# Card_Edge_Connector.net
KiCad netlist of a schematic drawn in Altium Designer
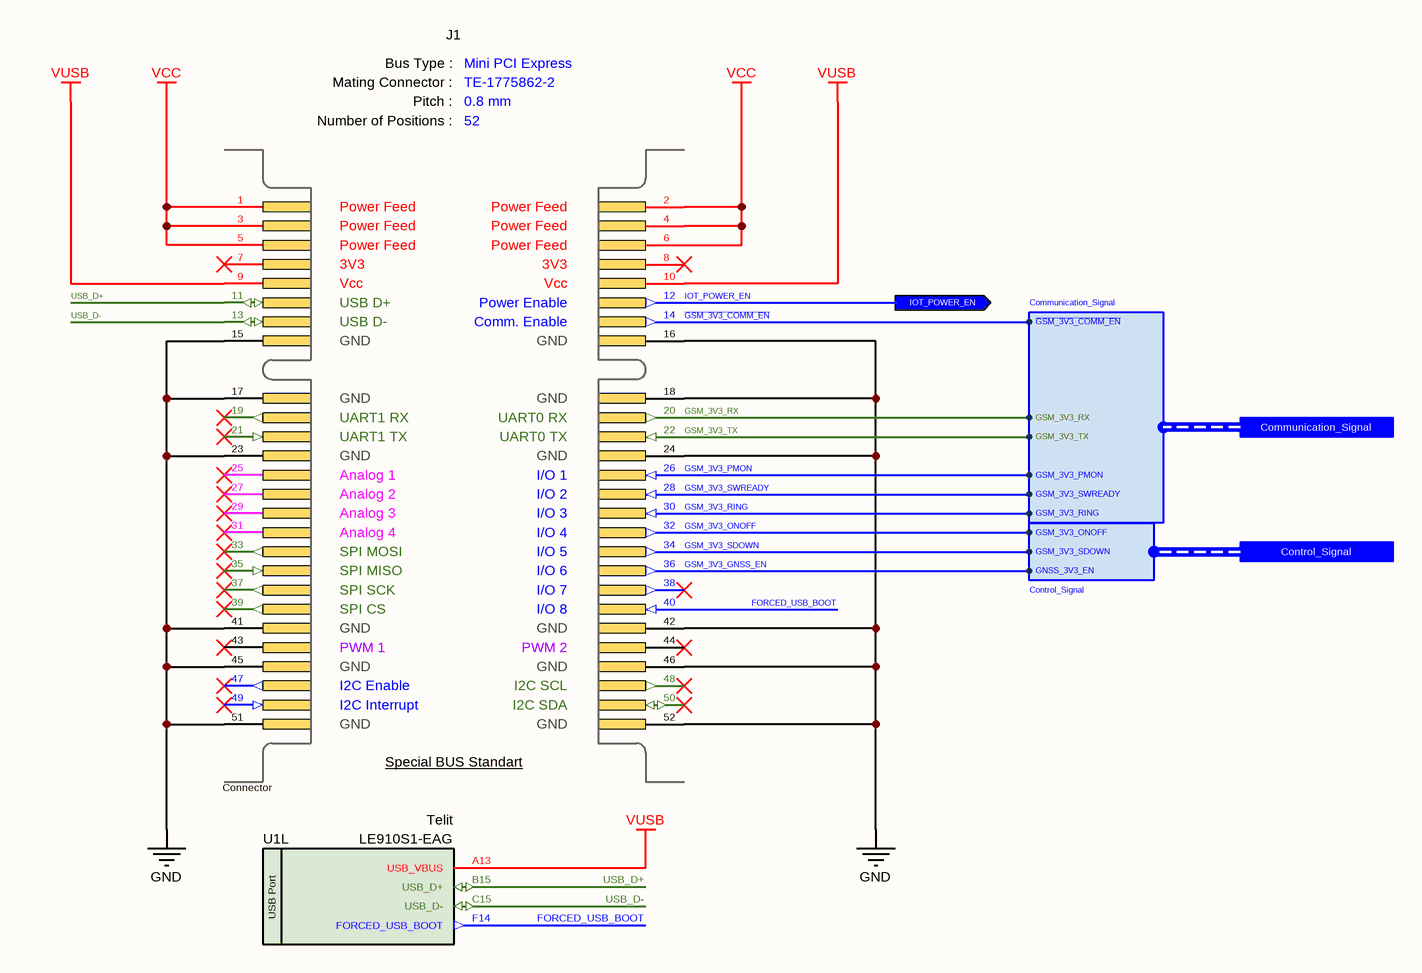
[diagram p0: Card Edge Connector.SchDoc]

(export (version "E")
  (design (tool "Eeschema 10.0.6"))
  (components
    (comp (ref "J1")
      (value "Connector - Mini PCI-E [Add-on]")
      (footprint "PCB - Mini PCI Express")
      (description "Mini PCI-Express gold finger connector.")
      (fields
        (field (name "BUS TYPE") "Mini PCI Express")
        (field (name "MATING CONNECTOR") "TE-1775862-2")
        (field (name "PITCH") "0.8 mm")
        (field (name "NUMBER OF POSITIONS") "52")
        (field (name "SYSTEM") "Connector")
      )
      (libsource (lib "P101DA_Library") (part "Connector - Mini PCI-E [Add-on]"))
    )
    (comp (ref "U1")
      (value "LE910S1-EAG LTE GSM Module")
      (footprint "LE910 GSM Modem")
      (description "Telit LE910S1-EAG GPRS/GNSS Module")
      (fields
        (field (name "MANUFACTURER PART NUMBER") "LE910S1-EAG")
        (field (name "MANUFACTURER NAME") "Telit")
      )
      (libsource (lib "P101DA_Library") (part "IC - LE910S1-EAG"))
    )
  )
  (nets
    (net (code "4") (name "/FORCED_USB_BOOT") (class "Default")
      (node (ref "J1") (pin "40") (pinfunction "Pin-40_40") (pintype "input"))
      (node (ref "U1") (pin "F14") (pinfunction "FORCED_USB_BOOT_F14") (pintype "output"))
    )
    (net (code "5") (name "/GSM_3V3_GNSS_EN") (class "Default")
      (node (ref "J1") (pin "36") (pinfunction "Pin-36_36") (pintype "output"))
    )
    (net (code "6") (name "/GSM_3V3_ONOFF") (class "Default")
      (node (ref "J1") (pin "32") (pinfunction "Pin-32_32") (pintype "output"))
    )
    (net (code "7") (name "/GSM_3V3_PMON") (class "Default")
      (node (ref "J1") (pin "26") (pinfunction "Pin-26_26") (pintype "input"))
    )
    (net (code "8") (name "/GSM_3V3_RING") (class "Default")
      (node (ref "J1") (pin "30") (pinfunction "Pin-30_30") (pintype "input"))
    )
    (net (code "9") (name "/GSM_3V3_RX") (class "Default")
      (node (ref "J1") (pin "20") (pinfunction "Pin-20_20") (pintype "output"))
    )
    (net (code "10") (name "/GSM_3V3_SDOWN") (class "Default")
      (node (ref "J1") (pin "34") (pinfunction "Pin-34_34") (pintype "output"))
    )
    (net (code "11") (name "/GSM_3V3_SWREADY") (class "Default")
      (node (ref "J1") (pin "28") (pinfunction "Pin-28_28") (pintype "input"))
    )
    (net (code "12") (name "/GSM_3V3_TX") (class "Default")
      (node (ref "J1") (pin "22") (pinfunction "Pin-22_22") (pintype "input"))
    )
    (net (code "13") (name "/IOT_POWER_EN") (class "Default")
      (node (ref "J1") (pin "12") (pinfunction "Pin-12_12") (pintype "output"))
    )
    (net (code "14") (name "/USB_D+") (class "Default")
      (node (ref "J1") (pin "11") (pinfunction "Pin-11_11") (pintype "bidirectional"))
      (node (ref "U1") (pin "B15") (pinfunction "USB_D+_B15") (pintype "bidirectional"))
    )
    (net (code "15") (name "/USB_D-") (class "Default")
      (node (ref "J1") (pin "13") (pinfunction "Pin-13_13") (pintype "bidirectional"))
      (node (ref "U1") (pin "C15") (pinfunction "USB_D-_C15") (pintype "bidirectional"))
    )
    (net (code "17") (name "/~{GSM_3V3_COMM_EN}") (class "Default")
      (node (ref "J1") (pin "14") (pinfunction "Pin-14_14") (pintype "output"))
    )
    (net (code "18") (name "GND") (class "Default")
      (node (ref "J1") (pin "15") (pinfunction "Pin-15_15") (pintype "power_in"))
      (node (ref "J1") (pin "16") (pinfunction "Pin-16_16") (pintype "power_in"))
      (node (ref "J1") (pin "17") (pinfunction "Pin-17_17") (pintype "power_in"))
      (node (ref "J1") (pin "18") (pinfunction "Pin-18_18") (pintype "power_in"))
      (node (ref "J1") (pin "23") (pinfunction "Pin-23_23") (pintype "power_in"))
      (node (ref "J1") (pin "24") (pinfunction "Pin-24_24") (pintype "power_in"))
      (node (ref "J1") (pin "41") (pinfunction "Pin-41_41") (pintype "power_in"))
      (node (ref "J1") (pin "42") (pinfunction "Pin-42_42") (pintype "power_in"))
      (node (ref "J1") (pin "45") (pinfunction "Pin-45_45") (pintype "power_in"))
      (node (ref "J1") (pin "46") (pinfunction "Pin-46_46") (pintype "power_in"))
      (node (ref "J1") (pin "51") (pinfunction "Pin-51_51") (pintype "power_in"))
      (node (ref "J1") (pin "52") (pinfunction "Pin-52_52") (pintype "power_in"))
    )
    (net (code "19") (name "VCC") (class "Default")
      (node (ref "J1") (pin "1") (pinfunction "Pin-1_1") (pintype "power_in"))
      (node (ref "J1") (pin "2") (pinfunction "Pin-2_2") (pintype "power_in"))
      (node (ref "J1") (pin "3") (pinfunction "Pin-3_3") (pintype "power_in"))
      (node (ref "J1") (pin "4") (pinfunction "Pin-4_4") (pintype "power_in"))
      (node (ref "J1") (pin "5") (pinfunction "Pin-5_5") (pintype "power_in"))
      (node (ref "J1") (pin "6") (pinfunction "Pin-6_6") (pintype "power_in"))
    )
    (net (code "20") (name "VUSB") (class "Default")
      (node (ref "J1") (pin "10") (pinfunction "Pin-10_10") (pintype "power_in"))
      (node (ref "J1") (pin "9") (pinfunction "Pin-9_9") (pintype "power_in"))
      (node (ref "U1") (pin "A13") (pinfunction "USB_VBUS_A13") (pintype "power_in"))
    )
    (net (code "21") (name "unconnected-(J1-Pin-7-Pad7)") (class "Default")
      (node (ref "J1") (pin "7") (pinfunction "Pin-7_7") (pintype "power_in+no_connect"))
    )
    (net (code "22") (name "unconnected-(J1-Pin-8-Pad8)") (class "Default")
      (node (ref "J1") (pin "8") (pinfunction "Pin-8_8") (pintype "power_in+no_connect"))
    )
    (net (code "23") (name "unconnected-(J1-Pin-19-Pad19)") (class "Default")
      (node (ref "J1") (pin "19") (pinfunction "Pin-19_19") (pintype "output+no_connect"))
    )
    (net (code "24") (name "unconnected-(J1-Pin-21-Pad21)") (class "Default")
      (node (ref "J1") (pin "21") (pinfunction "Pin-21_21") (pintype "input+no_connect"))
    )
    (net (code "25") (name "unconnected-(J1-Pin-25-Pad25)") (class "Default")
      (node (ref "J1") (pin "25") (pinfunction "Pin-25_25") (pintype "passive+no_connect"))
    )
    (net (code "26") (name "unconnected-(J1-Pin-27-Pad27)") (class "Default")
      (node (ref "J1") (pin "27") (pinfunction "Pin-27_27") (pintype "passive+no_connect"))
    )
    (net (code "27") (name "unconnected-(J1-Pin-29-Pad29)") (class "Default")
      (node (ref "J1") (pin "29") (pinfunction "Pin-29_29") (pintype "passive+no_connect"))
    )
    (net (code "28") (name "unconnected-(J1-Pin-31-Pad31)") (class "Default")
      (node (ref "J1") (pin "31") (pinfunction "Pin-31_31") (pintype "passive+no_connect"))
    )
    (net (code "29") (name "unconnected-(J1-Pin-33-Pad33)") (class "Default")
      (node (ref "J1") (pin "33") (pinfunction "Pin-33_33") (pintype "output+no_connect"))
    )
    (net (code "30") (name "unconnected-(J1-Pin-35-Pad35)") (class "Default")
      (node (ref "J1") (pin "35") (pinfunction "Pin-35_35") (pintype "input+no_connect"))
    )
    (net (code "31") (name "unconnected-(J1-Pin-37-Pad37)") (class "Default")
      (node (ref "J1") (pin "37") (pinfunction "Pin-37_37") (pintype "output+no_connect"))
    )
    (net (code "32") (name "unconnected-(J1-Pin-38-Pad38)") (class "Default")
      (node (ref "J1") (pin "38") (pinfunction "Pin-38_38") (pintype "output+no_connect"))
    )
    (net (code "33") (name "unconnected-(J1-Pin-39-Pad39)") (class "Default")
      (node (ref "J1") (pin "39") (pinfunction "Pin-39_39") (pintype "output+no_connect"))
    )
    (net (code "34") (name "unconnected-(J1-Pin-43-Pad43)") (class "Default")
      (node (ref "J1") (pin "43") (pinfunction "Pin-43_43") (pintype "passive+no_connect"))
    )
    (net (code "35") (name "unconnected-(J1-Pin-44-Pad44)") (class "Default")
      (node (ref "J1") (pin "44") (pinfunction "Pin-44_44") (pintype "passive+no_connect"))
    )
    (net (code "36") (name "unconnected-(J1-Pin-47-Pad47)") (class "Default")
      (node (ref "J1") (pin "47") (pinfunction "Pin-47_47") (pintype "output+no_connect"))
    )
    (net (code "37") (name "unconnected-(J1-Pin-48-Pad48)") (class "Default")
      (node (ref "J1") (pin "48") (pinfunction "Pin-48_48") (pintype "output+no_connect"))
    )
    (net (code "38") (name "unconnected-(J1-Pin-49-Pad49)") (class "Default")
      (node (ref "J1") (pin "49") (pinfunction "Pin-49_49") (pintype "input+no_connect"))
    )
    (net (code "39") (name "unconnected-(J1-Pin-50-Pad50)") (class "Default")
      (node (ref "J1") (pin "50") (pinfunction "Pin-50_50") (pintype "bidirectional+no_connect"))
    )
  )
)
